# IO.net
KiCad netlist of a schematic drawn in Altium Designer
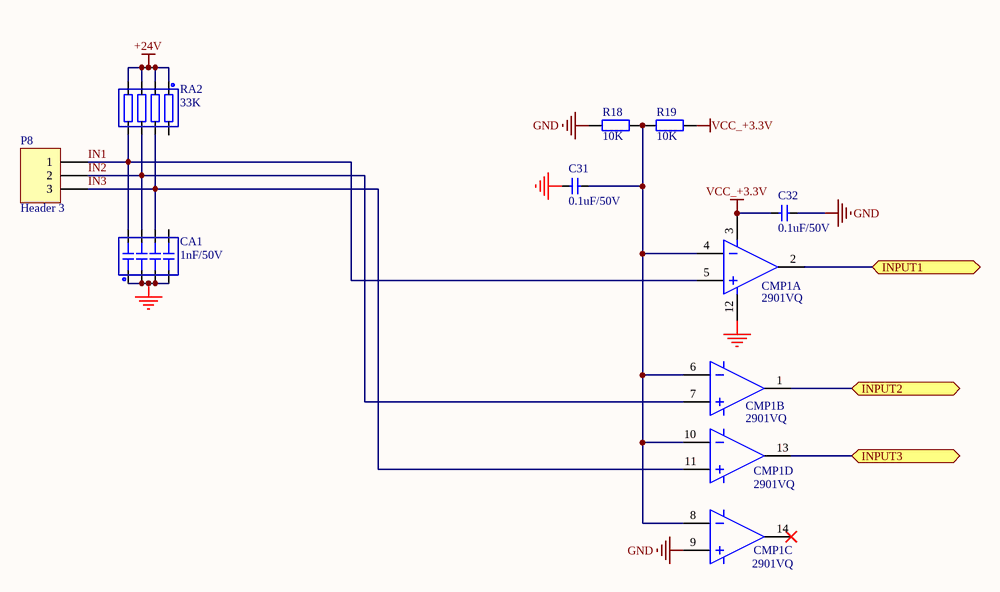
[diagram p0: IO.SchDoc]

(export (version "E")
  (design (tool "Eeschema 10.0.6"))
  (components
    (comp (ref "C31") (value "0.1uF/50V") (footprint "0603c") (libsource (lib "*") (part "CAP")))
    (comp (ref "C32") (value "0.1uF/50V") (footprint "0603C") (libsource (lib "0603C") (part "CAP")))
    (comp (ref "CA1") (value "1nF/50V") (footprint "RES_PACK_SMD_E") (libsource (lib "*") (part "CAP_PACK4")))
    (comp (ref "CMP1") (value "2901VQ") (footprint "TSSOP14") (libsource (lib "*") (part "LM339")))
    (comp (ref "P8")
      (value "Header 3")
      (footprint "HT396  3P")
      (description "Header, 3-Pin")
      (fields (field (name "PUBLISHER") "Altium Limited"))
      (libsource (lib "Miscellaneous Connectors") (part "Header 3"))
    )
    (comp (ref "R18") (value "10K") (footprint "0603R") (libsource (lib "*") (part "0603R")))
    (comp (ref "R19") (value "10K") (footprint "0603R") (libsource (lib "*") (part "0603R")))
    (comp (ref "RA2")
      (value "33K")
      (footprint "RES_PACK_SMD_E")
      (libsource (lib "SCT1212V100") (part "RESPACK4"))
    )
  )
  (nets
    (net (code "1") (name "+24V") (class "Default")
      (node (ref "RA2") (pin "1") (pintype "passive"))
      (node (ref "RA2") (pin "2") (pintype "passive"))
      (node (ref "RA2") (pin "3") (pintype "passive"))
      (node (ref "RA2") (pin "4") (pintype "passive"))
    )
    (net (code "2") (name "/IN1") (class "Default")
      (node (ref "CA1") (pin "8") (pintype "passive"))
      (node (ref "CMP1") (pin "5") (pintype "passive"))
      (node (ref "P8") (pin "1") (pinfunction "1_1") (pintype "passive"))
      (node (ref "RA2") (pin "5") (pintype "passive"))
    )
    (net (code "3") (name "/IN2") (class "Default")
      (node (ref "CA1") (pin "7") (pintype "passive"))
      (node (ref "CMP1") (pin "7") (pintype "passive"))
      (node (ref "P8") (pin "2") (pinfunction "2_2") (pintype "passive"))
      (node (ref "RA2") (pin "6") (pintype "passive"))
    )
    (net (code "4") (name "/IN3") (class "Default")
      (node (ref "CA1") (pin "6") (pintype "passive"))
      (node (ref "CMP1") (pin "11") (pintype "passive"))
      (node (ref "P8") (pin "3") (pinfunction "3_3") (pintype "passive"))
      (node (ref "RA2") (pin "7") (pintype "passive"))
    )
    (net (code "5") (name "/INPUT1") (class "Default") (node (ref "CMP1") (pin "2") (pintype "passive")))
    (net (code "6") (name "/INPUT2") (class "Default") (node (ref "CMP1") (pin "1") (pintype "passive")))
    (net (code "7") (name "/INPUT3") (class "Default") (node (ref "CMP1") (pin "13") (pintype "passive")))
    (net (code "8") (name "GND") (class "Default")
      (node (ref "C31") (pin "2") (pintype "passive"))
      (node (ref "C32") (pin "2") (pintype "passive"))
      (node (ref "CA1") (pin "1") (pintype "passive"))
      (node (ref "CA1") (pin "2") (pintype "passive"))
      (node (ref "CA1") (pin "3") (pintype "passive"))
      (node (ref "CA1") (pin "4") (pintype "passive"))
      (node (ref "CMP1") (pin "12") (pintype "passive"))
      (node (ref "CMP1") (pin "9") (pintype "passive"))
      (node (ref "R18") (pin "1") (pinfunction "1_1") (pintype "passive"))
    )
    (net (code "9") (name "Net-(C31-Pad1)") (class "Default")
      (node (ref "C31") (pin "1") (pintype "passive"))
      (node (ref "CMP1") (pin "10") (pintype "passive"))
      (node (ref "CMP1") (pin "4") (pintype "passive"))
      (node (ref "CMP1") (pin "6") (pintype "passive"))
      (node (ref "CMP1") (pin "8") (pintype "passive"))
      (node (ref "R18") (pin "2") (pinfunction "2_2") (pintype "passive"))
      (node (ref "R19") (pin "1") (pinfunction "1_1") (pintype "passive"))
    )
    (net (code "10") (name "VCC_+3.3V") (class "Default")
      (node (ref "C32") (pin "1") (pintype "passive"))
      (node (ref "CMP1") (pin "3") (pintype "passive"))
      (node (ref "R19") (pin "2") (pinfunction "2_2") (pintype "passive"))
    )
    (net (code "11") (name "unconnected-(CA1-Pad5)") (class "Default")
      (node (ref "CA1") (pin "5") (pintype "passive"))
    )
    (net (code "12") (name "unconnected-(CMP1-Pad14)") (class "Default")
      (node (ref "CMP1") (pin "14") (pintype "passive+no_connect"))
    )
    (net (code "13") (name "unconnected-(RA2-Pad8)") (class "Default")
      (node (ref "RA2") (pin "8") (pintype "passive"))
    )
  )
)
